# Sheet1.net
KiCad netlist of a schematic drawn in Altium Designer
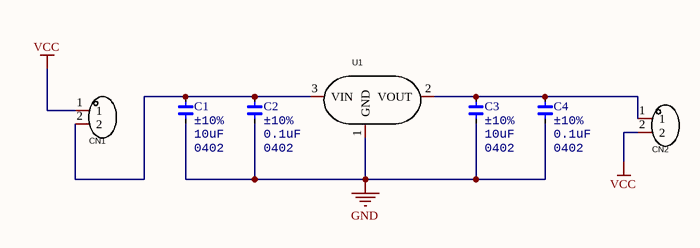
[diagram p0: Sheet1.SchDoc]

(export (version "E")
  (design (tool "Eeschema 10.0.6"))
  (components
    (comp (ref "C1")
      (value "10uF")
      (footprint "PCB_PassiveCap:CAP_0402")
      (description "Capacitor")
      (fields (field (name "NOTE") "±10%") (field (name "TYPE") "0402") (field (name "Comment") "C0402"))
      (libsource (lib "SCH_Passive") (part "Cap_0402"))
    )
    (comp (ref "C2")
      (value "0.1uF")
      (footprint "PCB_PassiveCap:CAP_0402")
      (description "Capacitor")
      (fields (field (name "NOTE") "±10%") (field (name "TYPE") "0402") (field (name "Comment") "C0402"))
      (libsource (lib "SCH_Passive") (part "Cap_0402"))
    )
    (comp (ref "C3")
      (value "10uF")
      (footprint "PCB_PassiveCap:CAP_0402")
      (description "Capacitor")
      (fields (field (name "NOTE") "±10%") (field (name "TYPE") "0402") (field (name "Comment") "C0402"))
      (libsource (lib "SCH_Passive") (part "Cap_0402"))
    )
    (comp (ref "C4")
      (value "0.1uF")
      (footprint "PCB_PassiveCap:CAP_0402")
      (description "Capacitor")
      (fields (field (name "NOTE") "±10%") (field (name "TYPE") "0402") (field (name "Comment") "C0402"))
      (libsource (lib "SCH_Passive") (part "Cap_0402"))
    )
    (comp (ref "CN1")
      (value "ZX-XH2.54-2PZZ")
      (footprint "CONN-TH_2P-P2.50_HX25003-2A")
      (fields (field (name "MANUFACTURER") "Megastar(兆星)"))
      (libsource (lib "Schlib1") (part "ZX-XH2.54-2PZZ"))
    )
    (comp (ref "CN2")
      (value "ZX-XH2.54-2PZZ")
      (footprint "CONN-TH_2P-P2.50_HX25003-2A")
      (fields (field (name "MANUFACTURER") "Megastar(兆星)"))
      (libsource (lib "Schlib1") (part "ZX-XH2.54-2PZZ"))
    )
    (comp (ref "U1")
      (value "AMS1117-3.3(XBLW)")
      (footprint "SOT-223-3_L6.5-W3.4-P2.30-LS7.0-BR-1")
      (fields (field (name "MANUFACTURER") "XBLW(芯伯乐)"))
      (libsource (lib "Schlib1") (part "AMS1117-3.3(XBLW)_C18906017"))
    )
  )
  (nets
    (net (code "1") (name "GND") (class "Default")
      (node (ref "C1") (pin "1") (pinfunction "1_1") (pintype "passive"))
      (node (ref "C2") (pin "1") (pinfunction "1_1") (pintype "passive"))
      (node (ref "C3") (pin "1") (pinfunction "1_1") (pintype "passive"))
      (node (ref "C4") (pin "1") (pinfunction "1_1") (pintype "passive"))
      (node (ref "U1") (pin "1") (pinfunction "GND_1") (pintype "passive"))
    )
    (net (code "2") (name "Net-(U1-VIN)") (class "Default")
      (node (ref "C1") (pin "2") (pinfunction "2_2") (pintype "passive"))
      (node (ref "C2") (pin "2") (pinfunction "2_2") (pintype "passive"))
      (node (ref "CN1") (pin "2") (pinfunction "2_2") (pintype "passive"))
      (node (ref "U1") (pin "3") (pinfunction "VIN_3") (pintype "passive"))
    )
    (net (code "3") (name "Net-(U1-VOUT)") (class "Default")
      (node (ref "C3") (pin "2") (pinfunction "2_2") (pintype "passive"))
      (node (ref "C4") (pin "2") (pinfunction "2_2") (pintype "passive"))
      (node (ref "CN2") (pin "1") (pinfunction "1_1") (pintype "passive"))
      (node (ref "U1") (pin "2") (pinfunction "VOUT_2") (pintype "passive"))
    )
    (net (code "4") (name "VCC") (class "Default")
      (node (ref "CN1") (pin "1") (pinfunction "1_1") (pintype "passive"))
      (node (ref "CN2") (pin "2") (pinfunction "2_2") (pintype "passive"))
    )
  )
)
